# PDB.net
KiCad netlist of a schematic drawn in Altium Designer
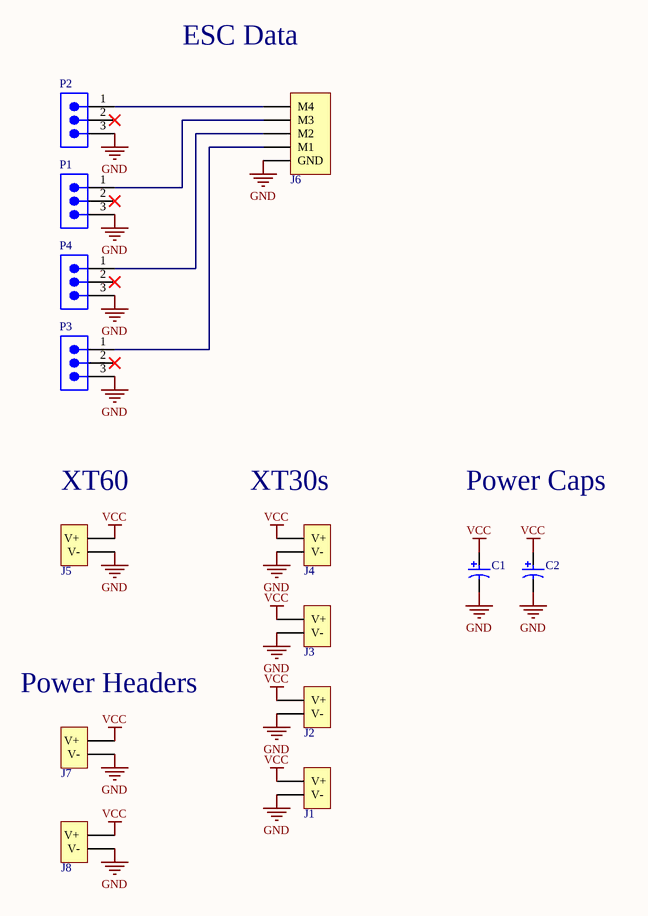
[diagram p0: PDB.SchDoc]

(export (version "E")
  (design (tool "Eeschema 10.0.6"))
  (components
    (comp (ref "C1")
      (value "ECA-1JHG471")
      (footprint "CAPPR65-500-2000X1250X2200")
      (fields (field (name "MANUFACTURER") "Panasonic"))
      (libsource (lib "Altium Content Vault") (part "CAP-P-2"))
    )
    (comp (ref "C2")
      (value "ECA-1JHG471")
      (footprint "CAPPR65-500-2000X1250X2200")
      (fields (field (name "MANUFACTURER") "Panasonic"))
      (libsource (lib "Altium Content Vault") (part "CAP-P-2"))
    )
    (comp (ref "J1") (value "XT30PB-M") (footprint "XT30PB-M") (libsource (lib "PDB") (part "XT30PB-M")))
    (comp (ref "J2") (value "XT30PB-M") (footprint "XT30PB-M") (libsource (lib "PDB") (part "XT30PB-M")))
    (comp (ref "J3") (value "XT30PB-M") (footprint "XT30PB-M") (libsource (lib "PDB") (part "XT30PB-M")))
    (comp (ref "J4") (value "XT30PB-M") (footprint "XT30PB-M") (libsource (lib "PDB") (part "XT30PB-M")))
    (comp (ref "J5") (value "xt60-M") (footprint "xt60-m") (libsource (lib "PDB") (part "xt60-M")))
    (comp (ref "J6")
      (value "motor to pixhawk conn")
      (footprint "motor to pixhawk headers")
      (libsource (lib "PDB") (part "motor to pixhawk conn"))
    )
    (comp (ref "J7")
      (value "power header")
      (footprint "power header")
      (libsource (lib "PDB") (part "power header"))
    )
    (comp (ref "J8")
      (value "power header")
      (footprint "power header")
      (libsource (lib "PDB") (part "power header"))
    )
    (comp (ref "P1")
      (value "TSW-103-08-T-S-RA")
      (footprint "SMTC-TSW-103-08-X-S-RA")
      (fields (field (name "MANUFACTURER") "Samtec"))
      (libsource (lib "Altium Content Vault") (part "SMTC-TSW-103-X-X-S-X"))
    )
    (comp (ref "P2")
      (value "TSW-103-08-T-S-RA")
      (footprint "SMTC-TSW-103-08-X-S-RA")
      (fields (field (name "MANUFACTURER") "Samtec"))
      (libsource (lib "Altium Content Vault") (part "SMTC-TSW-103-X-X-S-X"))
    )
    (comp (ref "P3")
      (value "TSW-103-08-T-S-RA")
      (footprint "SMTC-TSW-103-08-X-S-RA")
      (fields (field (name "MANUFACTURER") "Samtec"))
      (libsource (lib "Altium Content Vault") (part "SMTC-TSW-103-X-X-S-X"))
    )
    (comp (ref "P4")
      (value "TSW-103-08-T-S-RA")
      (footprint "SMTC-TSW-103-08-X-S-RA")
      (fields (field (name "MANUFACTURER") "Samtec"))
      (libsource (lib "Altium Content Vault") (part "SMTC-TSW-103-X-X-S-X"))
    )
  )
  (nets
    (net (code "1") (name "GND") (class "Default")
      (node (ref "C1") (pin "2") (pinfunction "2_2") (pintype "passive"))
      (node (ref "C2") (pin "2") (pinfunction "2_2") (pintype "passive"))
      (node (ref "J1") (pin "0") (pinfunction "V-_0") (pintype "passive"))
      (node (ref "J2") (pin "0") (pinfunction "V-_0") (pintype "passive"))
      (node (ref "J3") (pin "0") (pinfunction "V-_0") (pintype "passive"))
      (node (ref "J4") (pin "0") (pinfunction "V-_0") (pintype "passive"))
      (node (ref "J5") (pin "1") (pinfunction "V-_1") (pintype "passive"))
      (node (ref "J6") (pin "0") (pinfunction "GND_0") (pintype "passive"))
      (node (ref "J7") (pin "0") (pinfunction "V-_0") (pintype "passive"))
      (node (ref "J8") (pin "0") (pinfunction "V-_0") (pintype "passive"))
      (node (ref "P1") (pin "3") (pinfunction "3_3") (pintype "passive"))
      (node (ref "P2") (pin "3") (pinfunction "3_3") (pintype "passive"))
      (node (ref "P3") (pin "3") (pinfunction "3_3") (pintype "passive"))
      (node (ref "P4") (pin "3") (pinfunction "3_3") (pintype "passive"))
    )
    (net (code "2") (name "Net-(J6-M1)") (class "Default")
      (node (ref "J6") (pin "1") (pinfunction "M1_1") (pintype "passive"))
      (node (ref "P3") (pin "1") (pinfunction "1_1") (pintype "passive"))
    )
    (net (code "3") (name "Net-(J6-M2)") (class "Default")
      (node (ref "J6") (pin "2") (pinfunction "M2_2") (pintype "passive"))
      (node (ref "P4") (pin "1") (pinfunction "1_1") (pintype "passive"))
    )
    (net (code "4") (name "Net-(J6-M3)") (class "Default")
      (node (ref "J6") (pin "3") (pinfunction "M3_3") (pintype "passive"))
      (node (ref "P1") (pin "1") (pinfunction "1_1") (pintype "passive"))
    )
    (net (code "5") (name "Net-(J6-M4)") (class "Default")
      (node (ref "J6") (pin "4") (pinfunction "M4_4") (pintype "passive"))
      (node (ref "P2") (pin "1") (pinfunction "1_1") (pintype "passive"))
    )
    (net (code "6") (name "VCC") (class "Default")
      (node (ref "C1") (pin "1") (pinfunction "1_1") (pintype "passive"))
      (node (ref "C2") (pin "1") (pinfunction "1_1") (pintype "passive"))
      (node (ref "J1") (pin "1") (pinfunction "V+_1") (pintype "passive"))
      (node (ref "J2") (pin "1") (pinfunction "V+_1") (pintype "passive"))
      (node (ref "J3") (pin "1") (pinfunction "V+_1") (pintype "passive"))
      (node (ref "J4") (pin "1") (pinfunction "V+_1") (pintype "passive"))
      (node (ref "J5") (pin "2") (pinfunction "V+_2") (pintype "passive"))
      (node (ref "J7") (pin "1") (pinfunction "V+_1") (pintype "passive"))
      (node (ref "J8") (pin "1") (pinfunction "V+_1") (pintype "passive"))
    )
    (net (code "7") (name "unconnected-(P1-Pad2)") (class "Default")
      (node (ref "P1") (pin "2") (pinfunction "2_2") (pintype "passive+no_connect"))
    )
    (net (code "8") (name "unconnected-(P2-Pad2)") (class "Default")
      (node (ref "P2") (pin "2") (pinfunction "2_2") (pintype "passive+no_connect"))
    )
    (net (code "9") (name "unconnected-(P3-Pad2)") (class "Default")
      (node (ref "P3") (pin "2") (pinfunction "2_2") (pintype "passive+no_connect"))
    )
    (net (code "10") (name "unconnected-(P4-Pad2)") (class "Default")
      (node (ref "P4") (pin "2") (pinfunction "2_2") (pintype "passive+no_connect"))
    )
  )
)
